# SCHEM_FINAL.net
KiCad netlist of a schematic drawn in Altium Designer
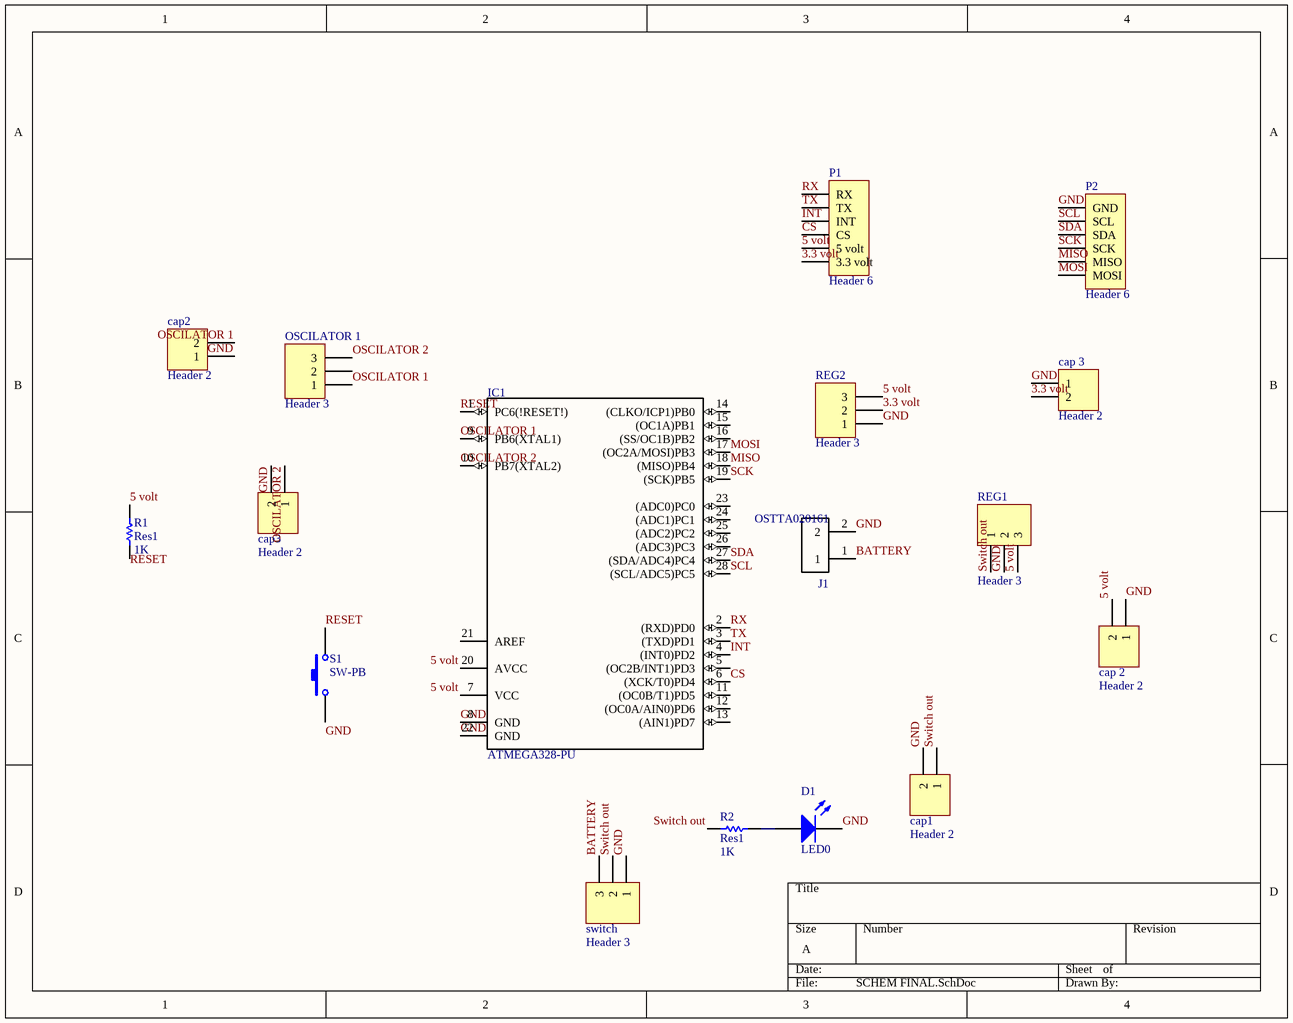
[diagram p0: SCHEM FINAL.SchDoc]

(export (version "E")
  (design (tool "Eeschema 10.0.6"))
  (components
    (comp (ref "cap 2")
      (value "Header 2")
      (footprint "HDR1X2")
      (description "Header, 2-Pin")
      (fields (field (name "PUBLISHER") "Altium Limited"))
      (libsource (lib "Miscellaneous Connectors") (part "Header 2"))
    )
    (comp (ref "cap 3")
      (value "Header 2")
      (footprint "HDR1X2")
      (description "Header, 2-Pin")
      (fields (field (name "PUBLISHER") "Altium Limited"))
      (libsource (lib "") (part "Header 2_2"))
    )
    (comp (ref "cap1")
      (value "Header 2")
      (footprint "HDR1X2")
      (description "Header, 2-Pin")
      (fields (field (name "PUBLISHER") "Altium Limited"))
      (libsource (lib "Miscellaneous Connectors") (part "Header 2"))
    )
    (comp (ref "cap2")
      (value "Header 2")
      (footprint "HDR1X2")
      (description "Header, 2-Pin")
      (fields (field (name "PUBLISHER") "Altium Limited"))
      (libsource (lib "") (part "Header 2_1"))
    )
    (comp (ref "cap3")
      (value "Header 2")
      (footprint "HDR1X2")
      (description "Header, 2-Pin")
      (fields (field (name "PUBLISHER") "Altium Limited"))
      (libsource (lib "Miscellaneous Connectors") (part "Header 2"))
    )
    (comp (ref "D1")
      (value "LED0")
      (footprint "LED-0")
      (description "Typical INFRARED GaAs LED")
      (fields (field (name "PUBLISHER") "Altium Limited"))
      (libsource (lib "Miscellaneous Devices") (part "LED0"))
    )
    (comp (ref "IC1")
      (value "ATMEGA328-PU")
      (footprint "*DIL28")
      (description "ATmega Series 20 MHz 32 KB Flash 2 KB SRAM 8-Bit Microcontroller - DIP-28")
      (fields (field (name "MF") "Microchip"))
      (libsource (lib "ATMEGA328-PU") (part "ATMEGA328-PU"))
    )
    (comp (ref "J1")
      (value "OSTTA020161")
      (footprint "*OST_OSTTA020161")
      (description "Connector Terminal Blocks 2 Position 5mm Solder Straight Thru-Hole 16A")
      (fields (field (name "MF") "On Shore"))
      (libsource (lib "OSTTA020161") (part "OSTTA020161"))
    )
    (comp (ref "OSCILATOR 1")
      (value "Header 3")
      (footprint "HDR1X3")
      (description "Header, 3-Pin")
      (fields (field (name "PUBLISHER") "Altium Limited"))
      (libsource (lib "Miscellaneous Connectors") (part "Header 3"))
    )
    (comp (ref "P1")
      (value "Header 6")
      (footprint "HDR1X6")
      (description "Header, 6-Pin")
      (fields (field (name "PUBLISHER") "Altium Limited"))
      (libsource (lib "Miscellaneous Connectors") (part "Header 6"))
    )
    (comp (ref "P2")
      (value "Header 6")
      (footprint "HDR1X6")
      (description "Header, 6-Pin")
      (fields (field (name "PUBLISHER") "Altium Limited"))
      (libsource (lib "Miscellaneous Connectors") (part "Header 6"))
    )
    (comp (ref "R1")
      (value "Res1")
      (footprint "AXIAL-0.3")
      (description "Resistor")
      (fields (field (name "ALTIUM_VALUE") "1K") (field (name "PUBLISHER") "Altium Limited"))
      (libsource (lib "Miscellaneous Devices") (part "Res1"))
    )
    (comp (ref "R2")
      (value "Res1")
      (footprint "AXIAL-0.3")
      (description "Resistor")
      (fields (field (name "ALTIUM_VALUE") "1K") (field (name "PUBLISHER") "Altium Limited"))
      (libsource (lib "Miscellaneous Devices") (part "Res1"))
    )
    (comp (ref "REG1")
      (value "Header 3")
      (footprint "HDR1X3")
      (description "Header, 3-Pin")
      (fields (field (name "PUBLISHER") "Altium Limited"))
      (libsource (lib "") (part "Header 3_1"))
    )
    (comp (ref "REG2")
      (value "Header 3")
      (footprint "HDR1X3")
      (description "Header, 3-Pin")
      (fields (field (name "PUBLISHER") "Altium Limited"))
      (libsource (lib "Miscellaneous Connectors") (part "Header 3"))
    )
    (comp (ref "S1")
      (value "SW-PB")
      (footprint "SPST-2")
      (description "Switch")
      (fields (field (name "PUBLISHER") "Altium Limited"))
      (libsource (lib "Miscellaneous Devices") (part "SW-PB"))
    )
    (comp (ref "switch")
      (value "Header 3")
      (footprint "HDR1X3")
      (description "Header, 3-Pin")
      (fields (field (name "PUBLISHER") "Altium Limited"))
      (libsource (lib "") (part "Header 3_2"))
    )
  )
  (nets
    (net (code "1") (name "/3.3 volt") (class "Default")
      (node (ref "P1") (pin "6") (pinfunction "MOSI_6") (pintype "passive"))
      (node (ref "REG2") (pin "2") (pinfunction "2_2") (pintype "passive"))
      (node (ref "cap 3") (pin "2") (pinfunction "2_2") (pintype "passive"))
    )
    (net (code "2") (name "/5 volt") (class "Default")
      (node (ref "IC1") (pin "20") (pinfunction "AVCC_20") (pintype "power_in"))
      (node (ref "IC1") (pin "7") (pinfunction "VCC_7") (pintype "power_in"))
      (node (ref "P1") (pin "5") (pinfunction "MISO_5") (pintype "passive"))
      (node (ref "R1") (pin "2") (pinfunction "2_2") (pintype "passive"))
      (node (ref "REG1") (pin "3") (pinfunction "3_3") (pintype "passive"))
      (node (ref "REG2") (pin "3") (pinfunction "3_3") (pintype "passive"))
      (node (ref "cap 2") (pin "2") (pinfunction "2_2") (pintype "passive"))
    )
    (net (code "3") (name "/BATTERY") (class "Default")
      (node (ref "J1") (pin "1") (pinfunction "1_1") (pintype "passive"))
      (node (ref "switch") (pin "3") (pinfunction "3_3") (pintype "passive"))
    )
    (net (code "4") (name "/CS") (class "Default")
      (node (ref "IC1") (pin "6") (pinfunction "(XCK/T0)PD4_6") (pintype "bidirectional"))
      (node (ref "P1") (pin "4") (pinfunction "SCK_4") (pintype "passive"))
    )
    (net (code "5") (name "/GND") (class "Default")
      (node (ref "D1") (pin "2") (pinfunction "K_2") (pintype "passive"))
      (node (ref "IC1") (pin "22") (pinfunction "GND_22") (pintype "power_in"))
      (node (ref "IC1") (pin "8") (pinfunction "GND_8") (pintype "power_in"))
      (node (ref "J1") (pin "2") (pinfunction "2_2") (pintype "passive"))
      (node (ref "P2") (pin "1") (pinfunction "GND_1") (pintype "passive"))
      (node (ref "REG1") (pin "2") (pinfunction "2_2") (pintype "passive"))
      (node (ref "REG2") (pin "1") (pinfunction "1_1") (pintype "passive"))
      (node (ref "S1") (pin "1") (pinfunction "1_1") (pintype "passive"))
      (node (ref "cap 2") (pin "1") (pinfunction "1_1") (pintype "passive"))
      (node (ref "cap 3") (pin "1") (pinfunction "1_1") (pintype "passive"))
      (node (ref "cap1") (pin "2") (pinfunction "2_2") (pintype "passive"))
      (node (ref "cap2") (pin "1") (pinfunction "1_1") (pintype "passive"))
      (node (ref "cap3") (pin "2") (pinfunction "2_2") (pintype "passive"))
      (node (ref "switch") (pin "1") (pinfunction "1_1") (pintype "passive"))
    )
    (net (code "6") (name "/INT") (class "Default")
      (node (ref "IC1") (pin "4") (pinfunction "(INT0)PD2_4") (pintype "bidirectional"))
      (node (ref "P1") (pin "3") (pinfunction "SDA_3") (pintype "passive"))
    )
    (net (code "7") (name "/MISO") (class "Default")
      (node (ref "IC1") (pin "18") (pinfunction "(MISO)PB4_18") (pintype "bidirectional"))
      (node (ref "P2") (pin "5") (pinfunction "MISO_5") (pintype "passive"))
    )
    (net (code "8") (name "/MOSI") (class "Default")
      (node (ref "IC1") (pin "17") (pinfunction "(OC2A/MOSI)PB3_17") (pintype "bidirectional"))
      (node (ref "P2") (pin "6") (pinfunction "MOSI_6") (pintype "passive"))
    )
    (net (code "9") (name "/OSCILATOR 1") (class "Default")
      (node (ref "IC1") (pin "9") (pinfunction "PB6(XTAL1)_9") (pintype "bidirectional"))
      (node (ref "OSCILATOR 1") (pin "1") (pinfunction "1_1") (pintype "passive"))
      (node (ref "cap2") (pin "2") (pinfunction "2_2") (pintype "passive"))
    )
    (net (code "10") (name "/OSCILATOR 2") (class "Default")
      (node (ref "IC1") (pin "10") (pinfunction "PB7(XTAL2)_10") (pintype "bidirectional"))
      (node (ref "OSCILATOR 1") (pin "3") (pinfunction "3_3") (pintype "passive"))
      (node (ref "cap3") (pin "1") (pinfunction "1_1") (pintype "passive"))
    )
    (net (code "11") (name "/RESET") (class "Default")
      (node (ref "IC1") (pin "1") (pinfunction "PC6(!RESET!)_1") (pintype "bidirectional"))
      (node (ref "R1") (pin "1") (pinfunction "1_1") (pintype "passive"))
      (node (ref "S1") (pin "2") (pinfunction "2_2") (pintype "passive"))
    )
    (net (code "12") (name "/RX") (class "Default")
      (node (ref "IC1") (pin "2") (pinfunction "(RXD)PD0_2") (pintype "bidirectional"))
      (node (ref "P1") (pin "1") (pinfunction "GND_1") (pintype "passive"))
    )
    (net (code "13") (name "/SCK") (class "Default")
      (node (ref "IC1") (pin "19") (pinfunction "(SCK)PB5_19") (pintype "bidirectional"))
      (node (ref "P2") (pin "4") (pinfunction "SCK_4") (pintype "passive"))
    )
    (net (code "14") (name "/SCL") (class "Default")
      (node (ref "IC1") (pin "28") (pinfunction "(SCL/ADC5)PC5_28") (pintype "bidirectional"))
      (node (ref "P2") (pin "2") (pinfunction "SCL_2") (pintype "passive"))
    )
    (net (code "15") (name "/SDA") (class "Default")
      (node (ref "IC1") (pin "27") (pinfunction "(SDA/ADC4)PC4_27") (pintype "bidirectional"))
      (node (ref "P2") (pin "3") (pinfunction "SDA_3") (pintype "passive"))
    )
    (net (code "16") (name "/Switch out") (class "Default")
      (node (ref "R2") (pin "1") (pinfunction "1_1") (pintype "passive"))
      (node (ref "REG1") (pin "1") (pinfunction "1_1") (pintype "passive"))
      (node (ref "cap1") (pin "1") (pinfunction "1_1") (pintype "passive"))
      (node (ref "switch") (pin "2") (pinfunction "2_2") (pintype "passive"))
    )
    (net (code "17") (name "/TX") (class "Default")
      (node (ref "IC1") (pin "3") (pinfunction "(TXD)PD1_3") (pintype "bidirectional"))
      (node (ref "P1") (pin "2") (pinfunction "SCL_2") (pintype "passive"))
    )
    (net (code "18") (name "Net-(D1-A)") (class "Default")
      (node (ref "D1") (pin "1") (pinfunction "A_1") (pintype "passive"))
      (node (ref "R2") (pin "2") (pinfunction "2_2") (pintype "passive"))
    )
    (net (code "19") (name "unconnected-(IC1-(ADC0)PC0-Pad23)") (class "Default")
      (node (ref "IC1") (pin "23") (pinfunction "(ADC0)PC0_23") (pintype "bidirectional"))
    )
    (net (code "20") (name "unconnected-(IC1-(ADC1)PC1-Pad24)") (class "Default")
      (node (ref "IC1") (pin "24") (pinfunction "(ADC1)PC1_24") (pintype "bidirectional"))
    )
    (net (code "21") (name "unconnected-(IC1-(ADC2)PC2-Pad25)") (class "Default")
      (node (ref "IC1") (pin "25") (pinfunction "(ADC2)PC2_25") (pintype "bidirectional"))
    )
    (net (code "22") (name "unconnected-(IC1-(ADC3)PC3-Pad26)") (class "Default")
      (node (ref "IC1") (pin "26") (pinfunction "(ADC3)PC3_26") (pintype "bidirectional"))
    )
    (net (code "23") (name "unconnected-(IC1-(AIN1)PD7-Pad13)") (class "Default")
      (node (ref "IC1") (pin "13") (pinfunction "(AIN1)PD7_13") (pintype "bidirectional"))
    )
    (net (code "24") (name "unconnected-(IC1-(CLKO{slash}ICP1)PB0-Pad14)") (class "Default")
      (node (ref "IC1") (pin "14") (pinfunction "(CLKO/ICP1)PB0_14") (pintype "bidirectional"))
    )
    (net (code "25") (name "unconnected-(IC1-(OC0A{slash}AIN0)PD6-Pad12)") (class "Default")
      (node (ref "IC1") (pin "12") (pinfunction "(OC0A/AIN0)PD6_12") (pintype "bidirectional"))
    )
    (net (code "26") (name "unconnected-(IC1-(OC0B{slash}T1)PD5-Pad11)") (class "Default")
      (node (ref "IC1") (pin "11") (pinfunction "(OC0B/T1)PD5_11") (pintype "bidirectional"))
    )
    (net (code "27") (name "unconnected-(IC1-(OC1A)PB1-Pad15)") (class "Default")
      (node (ref "IC1") (pin "15") (pinfunction "(OC1A)PB1_15") (pintype "bidirectional"))
    )
    (net (code "28") (name "unconnected-(IC1-(OC2B{slash}INT1)PD3-Pad5)") (class "Default")
      (node (ref "IC1") (pin "5") (pinfunction "(OC2B/INT1)PD3_5") (pintype "bidirectional"))
    )
    (net (code "29") (name "unconnected-(IC1-(SS{slash}OC1B)PB2-Pad16)") (class "Default")
      (node (ref "IC1") (pin "16") (pinfunction "(SS/OC1B)PB2_16") (pintype "bidirectional"))
    )
    (net (code "30") (name "unconnected-(IC1-AREF-Pad21)") (class "Default")
      (node (ref "IC1") (pin "21") (pinfunction "AREF_21") (pintype "passive"))
    )
    (net (code "31") (name "unconnected-(OSCILATOR 1-Pad2)") (class "Default")
      (node (ref "OSCILATOR 1") (pin "2") (pinfunction "2_2") (pintype "passive"))
    )
  )
)
